# Adafruit_VL530X_STEMMA_QT.net
KiCad netlist of a schematic drawn in EAGLE
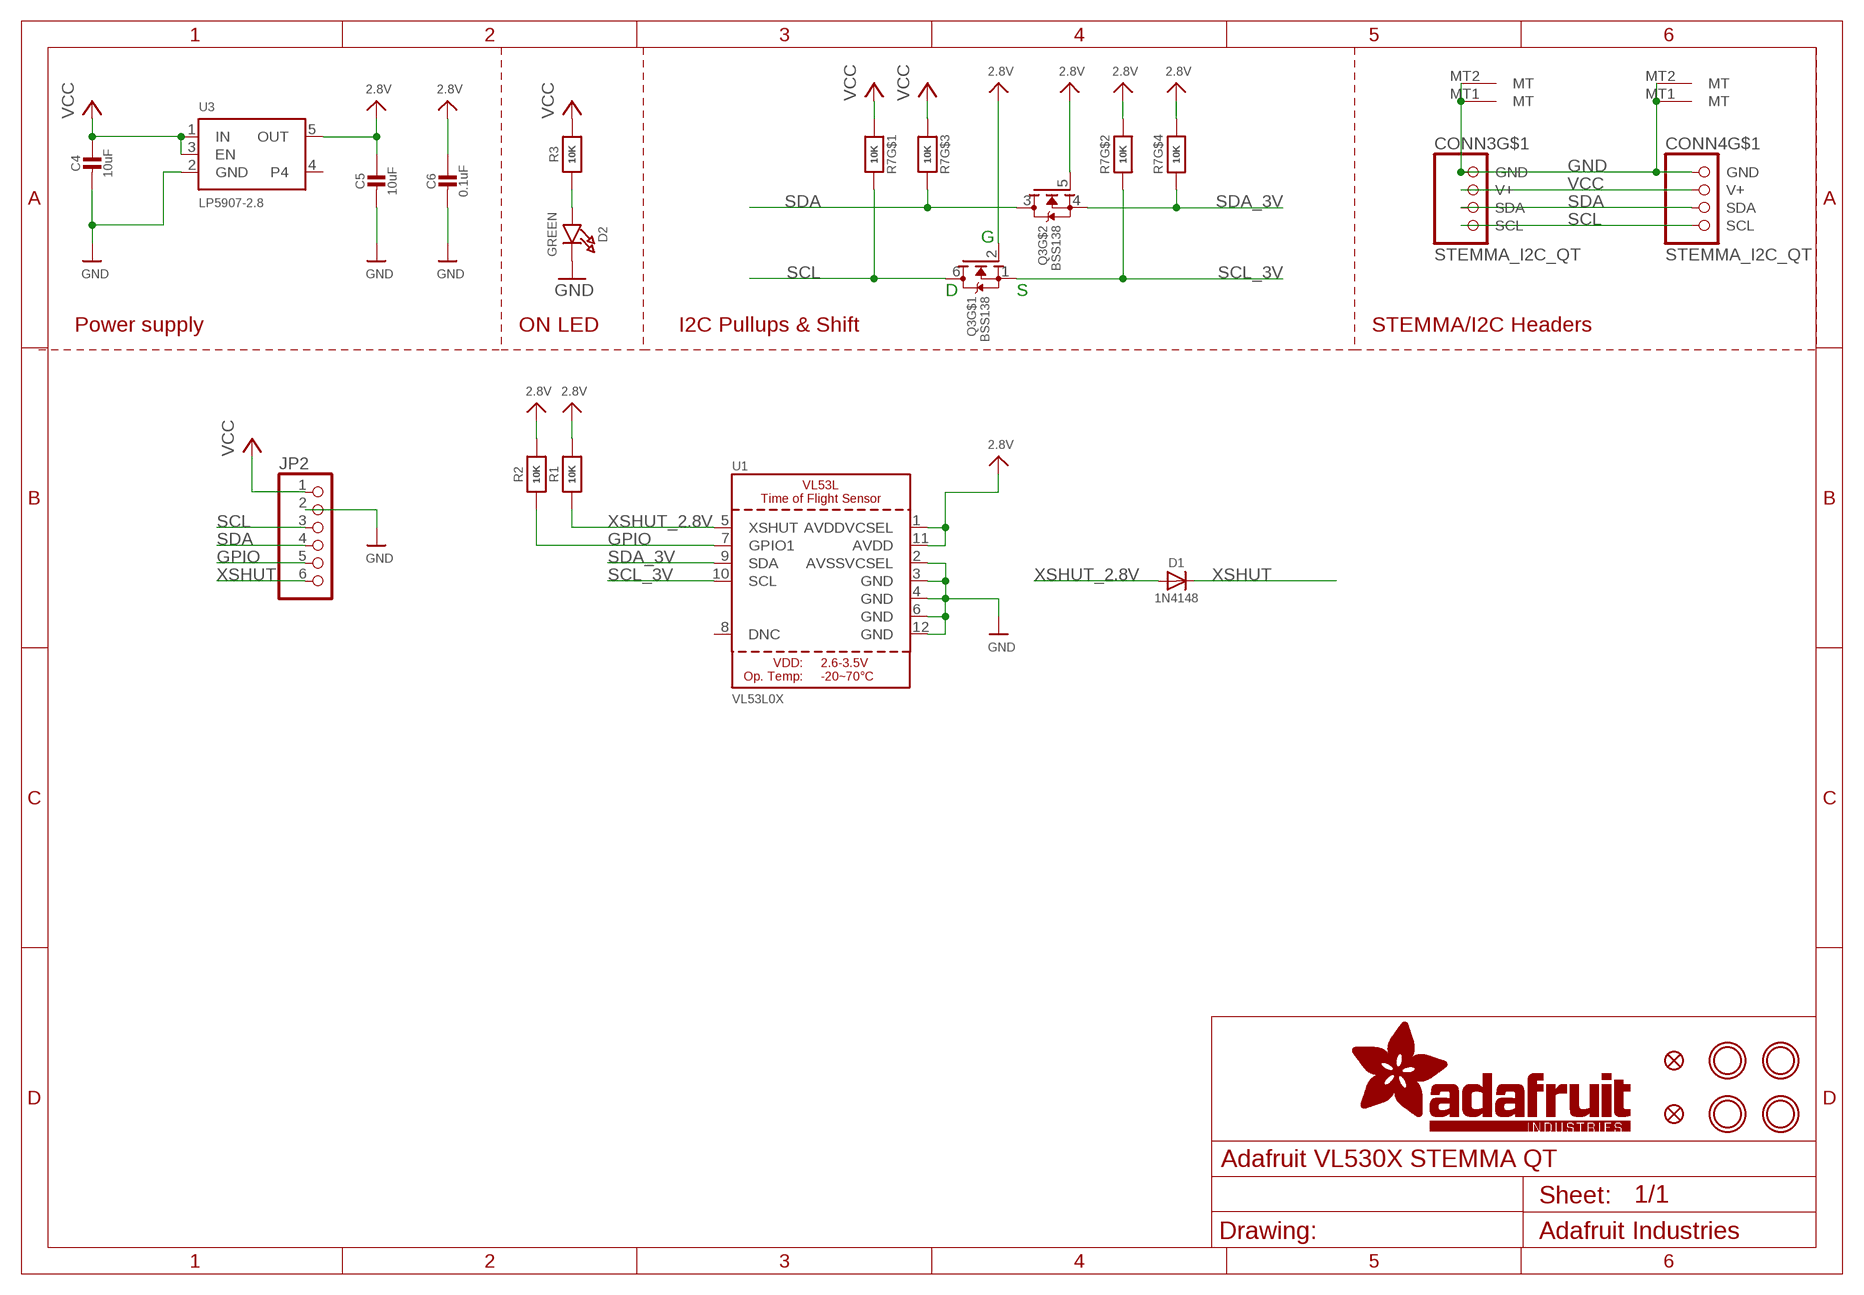
[diagram p0: schematic, sheet 1]

(export (version "E")
  (design (tool "Eeschema 10.0.6"))
  (components
    (comp (ref "C4")
      (value "10uF")
      (footprint "eagle-import:0805-NO")
      (libsource (lib "eagle-import") (part "CAP_CERAMIC0805-NOOUTLINE"))
    )
    (comp (ref "C5")
      (value "10uF")
      (footprint "eagle-import:0805-NO")
      (libsource (lib "eagle-import") (part "CAP_CERAMIC0805-NOOUTLINE"))
    )
    (comp (ref "C6")
      (value "0.1uF")
      (footprint "eagle-import:0603-NO")
      (libsource (lib "eagle-import") (part "CAP_CERAMIC0603_NO"))
    )
    (comp (ref "CONN3")
      (value "STEMMA_I2C_QT")
      (footprint "eagle-import:JST_SH4")
      (libsource (lib "eagle-import") (part "STEMMA_I2C_QT"))
    )
    (comp (ref "CONN4")
      (value "STEMMA_I2C_QT")
      (footprint "eagle-import:JST_SH4")
      (libsource (lib "eagle-import") (part "STEMMA_I2C_QT"))
    )
    (comp (ref "D1")
      (value "1N4148")
      (footprint "eagle-import:SOD-323")
      (libsource (lib "eagle-import") (part "DIODESOD-323"))
    )
    (comp (ref "D2")
      (value "GREEN")
      (footprint "eagle-import:CHIPLED_0603_NOOUTLINE")
      (libsource (lib "eagle-import") (part "LED0603_NOOUTLINE"))
    )
    (comp (ref "FID1")
      (value "FIDUCIAL_1MM")
      (footprint "eagle-import:FIDUCIAL_1MM")
      (libsource (lib "eagle-import") (part "FIDUCIAL_1MM"))
    )
    (comp (ref "FID4")
      (value "FIDUCIAL_1MM")
      (footprint "eagle-import:FIDUCIAL_1MM")
      (libsource (lib "eagle-import") (part "FIDUCIAL_1MM"))
    )
    (comp (ref "JP2")
      (value "HEADER-1X670MIL")
      (footprint "eagle-import:1X06_ROUND_70")
      (libsource (lib "eagle-import") (part "HEADER-1X670MIL"))
    )
    (comp (ref "Q3")
      (value "BSS138")
      (footprint "eagle-import:SOT363")
      (libsource (lib "eagle-import") (part "MOSFET-N_DUAL"))
    )
    (comp (ref "R1")
      (value "10K")
      (footprint "eagle-import:0603-NO")
      (libsource (lib "eagle-import") (part "RESISTOR_0603_NOOUT"))
    )
    (comp (ref "R2")
      (value "10K")
      (footprint "eagle-import:0603-NO")
      (libsource (lib "eagle-import") (part "RESISTOR_0603_NOOUT"))
    )
    (comp (ref "R3")
      (value "10K")
      (footprint "eagle-import:0603-NO")
      (libsource (lib "eagle-import") (part "RESISTOR_0603_NOOUT"))
    )
    (comp (ref "R7")
      (value "10K")
      (footprint "eagle-import:RESPACK_4X0603")
      (libsource (lib "eagle-import") (part "RESISTOR_4PACK"))
    )
    (comp (ref "U$30")
      (value "MOUNTINGHOLE2.5")
      (footprint "eagle-import:MOUNTINGHOLE_2.5_PLATED")
      (libsource (lib "eagle-import") (part "MOUNTINGHOLE2.5"))
    )
    (comp (ref "U$31")
      (value "MOUNTINGHOLE2.5")
      (footprint "eagle-import:MOUNTINGHOLE_2.5_PLATED")
      (libsource (lib "eagle-import") (part "MOUNTINGHOLE2.5"))
    )
    (comp (ref "U$33")
      (value "MOUNTINGHOLE2.5")
      (footprint "eagle-import:MOUNTINGHOLE_2.5_PLATED")
      (libsource (lib "eagle-import") (part "MOUNTINGHOLE2.5"))
    )
    (comp (ref "U$34")
      (value "MOUNTINGHOLE2.5")
      (footprint "eagle-import:MOUNTINGHOLE_2.5_PLATED")
      (libsource (lib "eagle-import") (part "MOUNTINGHOLE2.5"))
    )
    (comp (ref "U1")
      (value "VL53L0X")
      (footprint "eagle-import:LGA12_ST")
      (libsource (lib "eagle-import") (part "VL53L0X"))
    )
    (comp (ref "U3")
      (value "LP5907-2.8")
      (footprint "eagle-import:SOT23-5")
      (libsource (lib "eagle-import") (part "VREG_SOT23-5"))
    )
  )
  (nets
    (net (code "1") (name "/GPIO") (class "Default")
      (node (ref "JP2") (pin "5") (pinfunction "5_5") (pintype "passive"))
      (node (ref "R2") (pin "1") (pinfunction "1_1") (pintype "passive"))
      (node (ref "U1") (pin "7") (pinfunction "GPIO1_7") (pintype "output"))
    )
    (net (code "2") (name "/SCL") (class "Default")
      (node (ref "CONN3") (pin "4") (pinfunction "SCL_4") (pintype "passive"))
      (node (ref "CONN4") (pin "4") (pinfunction "SCL_4") (pintype "passive"))
      (node (ref "JP2") (pin "3") (pinfunction "3_3") (pintype "passive"))
      (node (ref "Q3") (pin "6") (pinfunction "D_6") (pintype "bidirectional"))
      (node (ref "R7") (pin "8") (pinfunction "2_8") (pintype "passive"))
    )
    (net (code "3") (name "/SCL_3V") (class "Default")
      (node (ref "Q3") (pin "1") (pinfunction "S_1") (pintype "bidirectional"))
      (node (ref "R7") (pin "7") (pinfunction "2_7") (pintype "passive"))
      (node (ref "U1") (pin "10") (pinfunction "SCL_10") (pintype "open_collector"))
    )
    (net (code "4") (name "/SDA") (class "Default")
      (node (ref "CONN3") (pin "3") (pinfunction "SDA_3") (pintype "passive"))
      (node (ref "CONN4") (pin "3") (pinfunction "SDA_3") (pintype "passive"))
      (node (ref "JP2") (pin "4") (pinfunction "4_4") (pintype "passive"))
      (node (ref "Q3") (pin "3") (pinfunction "D_3") (pintype "bidirectional"))
      (node (ref "R7") (pin "6") (pinfunction "2_6") (pintype "passive"))
    )
    (net (code "5") (name "/SDA_3V") (class "Default")
      (node (ref "Q3") (pin "4") (pinfunction "S_4") (pintype "bidirectional"))
      (node (ref "R7") (pin "5") (pinfunction "2_5") (pintype "passive"))
      (node (ref "U1") (pin "9") (pinfunction "SDA_9") (pintype "open_collector"))
    )
    (net (code "6") (name "/XSHUT") (class "Default")
      (node (ref "D1") (pin "C") (pinfunction "C_C") (pintype "passive"))
      (node (ref "JP2") (pin "6") (pinfunction "6_6") (pintype "passive"))
    )
    (net (code "7") (name "/XSHUT_2.8V") (class "Default")
      (node (ref "D1") (pin "A") (pinfunction "A_A") (pintype "passive"))
      (node (ref "R1") (pin "1") (pinfunction "1_1") (pintype "passive"))
      (node (ref "U1") (pin "5") (pinfunction "XSHUT_5") (pintype "input"))
    )
    (net (code "8") (name "2.8V") (class "Default")
      (node (ref "C5") (pin "1") (pinfunction "1_1") (pintype "passive"))
      (node (ref "C6") (pin "1") (pinfunction "1_1") (pintype "passive"))
      (node (ref "Q3") (pin "2") (pinfunction "G_2") (pintype "bidirectional"))
      (node (ref "Q3") (pin "5") (pinfunction "G_5") (pintype "bidirectional"))
      (node (ref "R1") (pin "2") (pinfunction "2_2") (pintype "passive"))
      (node (ref "R2") (pin "2") (pinfunction "2_2") (pintype "passive"))
      (node (ref "R7") (pin "2") (pinfunction "1_2") (pintype "passive"))
      (node (ref "R7") (pin "4") (pinfunction "1_4") (pintype "passive"))
      (node (ref "U1") (pin "1") (pinfunction "AVDDVCSEL_1") (pintype "power_in"))
      (node (ref "U1") (pin "11") (pinfunction "AVDD_11") (pintype "power_in"))
      (node (ref "U3") (pin "5") (pinfunction "OUT_5") (pintype "power_in"))
    )
    (net (code "9") (name "GND") (class "Default")
      (node (ref "C4") (pin "2") (pinfunction "2_2") (pintype "passive"))
      (node (ref "C5") (pin "2") (pinfunction "2_2") (pintype "passive"))
      (node (ref "C6") (pin "2") (pinfunction "2_2") (pintype "passive"))
      (node (ref "CONN3") (pin "1") (pinfunction "GND_1") (pintype "passive"))
      (node (ref "CONN3") (pin "MT1") (pinfunction "MT_MT1") (pintype "bidirectional"))
      (node (ref "CONN3") (pin "MT2") (pinfunction "MT_MT2") (pintype "bidirectional"))
      (node (ref "CONN4") (pin "1") (pinfunction "GND_1") (pintype "passive"))
      (node (ref "CONN4") (pin "MT1") (pinfunction "MT_MT1") (pintype "bidirectional"))
      (node (ref "CONN4") (pin "MT2") (pinfunction "MT_MT2") (pintype "bidirectional"))
      (node (ref "D2") (pin "C") (pinfunction "C_C") (pintype "passive"))
      (node (ref "JP2") (pin "2") (pinfunction "2_2") (pintype "passive"))
      (node (ref "U1") (pin "12") (pinfunction "GND_12") (pintype "power_in"))
      (node (ref "U1") (pin "2") (pinfunction "AVSSVCSEL_2") (pintype "power_in"))
      (node (ref "U1") (pin "3") (pinfunction "GND_3") (pintype "power_in"))
      (node (ref "U1") (pin "4") (pinfunction "GND_4") (pintype "power_in"))
      (node (ref "U1") (pin "6") (pinfunction "GND_6") (pintype "power_in"))
      (node (ref "U3") (pin "2") (pinfunction "GND_2") (pintype "power_in"))
    )
    (net (code "10") (name "Net-(D2-PadA)") (class "Default")
      (node (ref "D2") (pin "A") (pinfunction "A_A") (pintype "passive"))
      (node (ref "R3") (pin "1") (pinfunction "1_1") (pintype "passive"))
    )
    (net (code "11") (name "VCC") (class "Default")
      (node (ref "C4") (pin "1") (pinfunction "1_1") (pintype "passive"))
      (node (ref "CONN3") (pin "2") (pinfunction "V+_2") (pintype "passive"))
      (node (ref "CONN4") (pin "2") (pinfunction "V+_2") (pintype "passive"))
      (node (ref "JP2") (pin "1") (pinfunction "1_1") (pintype "passive"))
      (node (ref "R3") (pin "2") (pinfunction "2_2") (pintype "passive"))
      (node (ref "R7") (pin "1") (pinfunction "1_1") (pintype "passive"))
      (node (ref "R7") (pin "3") (pinfunction "1_3") (pintype "passive"))
      (node (ref "U3") (pin "1") (pinfunction "IN_1") (pintype "power_in"))
      (node (ref "U3") (pin "3") (pinfunction "EN_3") (pintype "input"))
    )
    (net (code "12") (name "unconnected-(U1-DNC-Pad8)") (class "Default")
      (node (ref "U1") (pin "8") (pinfunction "DNC_8") (pintype "no_connect"))
    )
    (net (code "13") (name "unconnected-(U3-P4-Pad4)") (class "Default")
      (node (ref "U3") (pin "4") (pinfunction "P4_4") (pintype "bidirectional"))
    )
  )
)
